# Solar_charger_v2.net
KiCad netlist of a schematic drawn in EAGLE
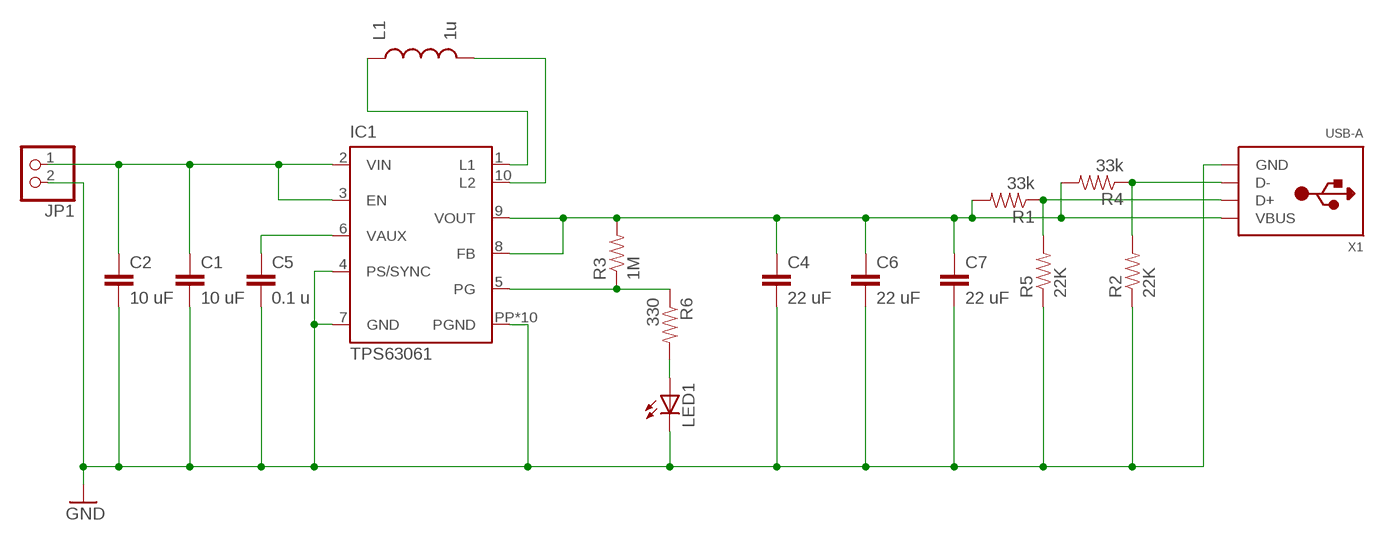
[diagram p0: schematic, sheet 1]

(export (version "E")
  (design (tool "Eeschema 10.0.6"))
  (components
    (comp (ref "C1")
      (value "10 uF")
      (footprint "eagle-import:1206")
      (libsource (lib "eagle-import") (part "CAP1206"))
    )
    (comp (ref "C2")
      (value "10 uF")
      (footprint "eagle-import:1206")
      (libsource (lib "eagle-import") (part "CAP1206"))
    )
    (comp (ref "C4")
      (value "22 uF")
      (footprint "eagle-import:1206")
      (libsource (lib "eagle-import") (part "CAP1206"))
    )
    (comp (ref "C5")
      (value "0.1 u")
      (footprint "eagle-import:1206")
      (libsource (lib "eagle-import") (part "CAP1206"))
    )
    (comp (ref "C6")
      (value "22 uF")
      (footprint "eagle-import:1206")
      (libsource (lib "eagle-import") (part "CAP1206"))
    )
    (comp (ref "C7")
      (value "22 uF")
      (footprint "eagle-import:1206")
      (libsource (lib "eagle-import") (part "CAP1206"))
    )
    (comp (ref "IC1")
      (value "TPS63061")
      (footprint "eagle-import:DSC-S-PWSON-N10")
      (libsource (lib "eagle-import") (part "TPS63061"))
    )
    (comp (ref "JP1")
      (value "JST_2PIN-SMT")
      (footprint "eagle-import:JST-PH-2-SMT")
      (libsource (lib "eagle-import") (part "JST_2PIN-SMT"))
    )
    (comp (ref "L1")
      (value "1u")
      (footprint "eagle-import:1210")
      (libsource (lib "eagle-import") (part "INDUCTOR1210"))
    )
    (comp (ref "LED1")
      (value "LEDSML0805")
      (footprint "eagle-import:SML0805")
      (libsource (lib "eagle-import") (part "LEDSML0805"))
    )
    (comp (ref "R1")
      (value "33k")
      (footprint "eagle-import:1206")
      (libsource (lib "eagle-import") (part "RESISTOR1206"))
    )
    (comp (ref "R2")
      (value "22K")
      (footprint "eagle-import:1206")
      (libsource (lib "eagle-import") (part "RESISTOR1206"))
    )
    (comp (ref "R3")
      (value "1M")
      (footprint "eagle-import:1206")
      (libsource (lib "eagle-import") (part "RESISTOR1206"))
    )
    (comp (ref "R4")
      (value "33k")
      (footprint "eagle-import:1206")
      (libsource (lib "eagle-import") (part "RESISTOR1206"))
    )
    (comp (ref "R5")
      (value "22K")
      (footprint "eagle-import:1206")
      (libsource (lib "eagle-import") (part "RESISTOR1206"))
    )
    (comp (ref "R6")
      (value "330")
      (footprint "eagle-import:1206")
      (libsource (lib "eagle-import") (part "RESISTOR1206"))
    )
    (comp (ref "X1")
      (value "USB-A")
      (footprint "eagle-import:MOLEX_480371000")
      (libsource (lib "eagle-import") (part "USB-A"))
    )
  )
  (nets
    (net (code "1") (name "GND") (class "Default")
      (node (ref "C1") (pin "2") (pinfunction "2_2") (pintype "passive"))
      (node (ref "C2") (pin "2") (pinfunction "2_2") (pintype "passive"))
      (node (ref "C4") (pin "2") (pinfunction "2_2") (pintype "passive"))
      (node (ref "C5") (pin "2") (pinfunction "2_2") (pintype "passive"))
      (node (ref "C6") (pin "2") (pinfunction "2_2") (pintype "passive"))
      (node (ref "C7") (pin "2") (pinfunction "2_2") (pintype "passive"))
      (node (ref "IC1") (pin "4") (pinfunction "PS/SYNC_4") (pintype "input"))
      (node (ref "IC1") (pin "7") (pinfunction "GND_7") (pintype "input"))
      (node (ref "IC1") (pin "PP") (pinfunction "PGND_PP") (pintype "power_in"))
      (node (ref "IC1") (pin "PP@1") (pinfunction "PGND_PP@1") (pintype "power_in"))
      (node (ref "IC1") (pin "PP@10") (pinfunction "PGND_PP@10") (pintype "power_in"))
      (node (ref "IC1") (pin "PP@2") (pinfunction "PGND_PP@2") (pintype "power_in"))
      (node (ref "IC1") (pin "PP@3") (pinfunction "PGND_PP@3") (pintype "power_in"))
      (node (ref "IC1") (pin "PP@4") (pinfunction "PGND_PP@4") (pintype "power_in"))
      (node (ref "IC1") (pin "PP@5") (pinfunction "PGND_PP@5") (pintype "power_in"))
      (node (ref "IC1") (pin "PP@7") (pinfunction "PGND_PP@7") (pintype "power_in"))
      (node (ref "IC1") (pin "PP@8") (pinfunction "PGND_PP@8") (pintype "power_in"))
      (node (ref "IC1") (pin "PP@9") (pinfunction "PGND_PP@9") (pintype "power_in"))
      (node (ref "JP1") (pin "2") (pinfunction "1_2") (pintype "passive"))
      (node (ref "LED1") (pin "C") (pinfunction "C_C") (pintype "passive"))
      (node (ref "R2") (pin "1") (pinfunction "1_1") (pintype "passive"))
      (node (ref "R5") (pin "1") (pinfunction "1_1") (pintype "passive"))
      (node (ref "X1") (pin "4") (pinfunction "GND_4") (pintype "power_in"))
    )
    (net (code "2") (name "Net-(IC1-EN)") (class "Default")
      (node (ref "C1") (pin "1") (pinfunction "1_1") (pintype "passive"))
      (node (ref "C2") (pin "1") (pinfunction "1_1") (pintype "passive"))
      (node (ref "IC1") (pin "2") (pinfunction "VIN_2") (pintype "input"))
      (node (ref "IC1") (pin "3") (pinfunction "EN_3") (pintype "input"))
      (node (ref "JP1") (pin "1") (pinfunction "2_1") (pintype "passive"))
    )
    (net (code "3") (name "Net-(IC1-FB)") (class "Default")
      (node (ref "C4") (pin "1") (pinfunction "1_1") (pintype "passive"))
      (node (ref "C6") (pin "1") (pinfunction "1_1") (pintype "passive"))
      (node (ref "C7") (pin "1") (pinfunction "1_1") (pintype "passive"))
      (node (ref "IC1") (pin "8") (pinfunction "FB_8") (pintype "input"))
      (node (ref "IC1") (pin "9") (pinfunction "VOUT_9") (pintype "output"))
      (node (ref "R1") (pin "2") (pinfunction "2_2") (pintype "passive"))
      (node (ref "R3") (pin "2") (pinfunction "2_2") (pintype "passive"))
      (node (ref "R4") (pin "2") (pinfunction "2_2") (pintype "passive"))
      (node (ref "X1") (pin "1") (pinfunction "VBUS_1") (pintype "power_in"))
    )
    (net (code "4") (name "Net-(IC1-L1)") (class "Default")
      (node (ref "IC1") (pin "1") (pinfunction "L1_1") (pintype "input"))
      (node (ref "L1") (pin "1") (pinfunction "1_1") (pintype "passive"))
    )
    (net (code "5") (name "Net-(IC1-L2)") (class "Default")
      (node (ref "IC1") (pin "10") (pinfunction "L2_10") (pintype "input"))
      (node (ref "L1") (pin "2") (pinfunction "2_2") (pintype "passive"))
    )
    (net (code "6") (name "Net-(IC1-PG)") (class "Default")
      (node (ref "IC1") (pin "5") (pinfunction "PG_5") (pintype "output"))
      (node (ref "R3") (pin "1") (pinfunction "1_1") (pintype "passive"))
      (node (ref "R6") (pin "1") (pinfunction "1_1") (pintype "passive"))
    )
    (net (code "7") (name "Net-(IC1-VAUX)") (class "Default")
      (node (ref "C5") (pin "1") (pinfunction "1_1") (pintype "passive"))
      (node (ref "IC1") (pin "6") (pinfunction "VAUX_6") (pintype "power_in"))
    )
    (net (code "8") (name "Net-(LED1-PadA)") (class "Default")
      (node (ref "LED1") (pin "A") (pinfunction "A_A") (pintype "passive"))
      (node (ref "R6") (pin "2") (pinfunction "2_2") (pintype "passive"))
    )
    (net (code "9") (name "Net-(X1-D+)") (class "Default")
      (node (ref "R1") (pin "1") (pinfunction "1_1") (pintype "passive"))
      (node (ref "R5") (pin "2") (pinfunction "2_2") (pintype "passive"))
      (node (ref "X1") (pin "3") (pinfunction "D+_3") (pintype "bidirectional"))
    )
    (net (code "10") (name "Net-(X1-D-)") (class "Default")
      (node (ref "R2") (pin "2") (pinfunction "2_2") (pintype "passive"))
      (node (ref "R4") (pin "1") (pinfunction "1_1") (pintype "passive"))
      (node (ref "X1") (pin "2") (pinfunction "D-_2") (pintype "bidirectional"))
    )
  )
)
